# RF_REVE_2.net
KiCad netlist of a schematic drawn in Altium Designer
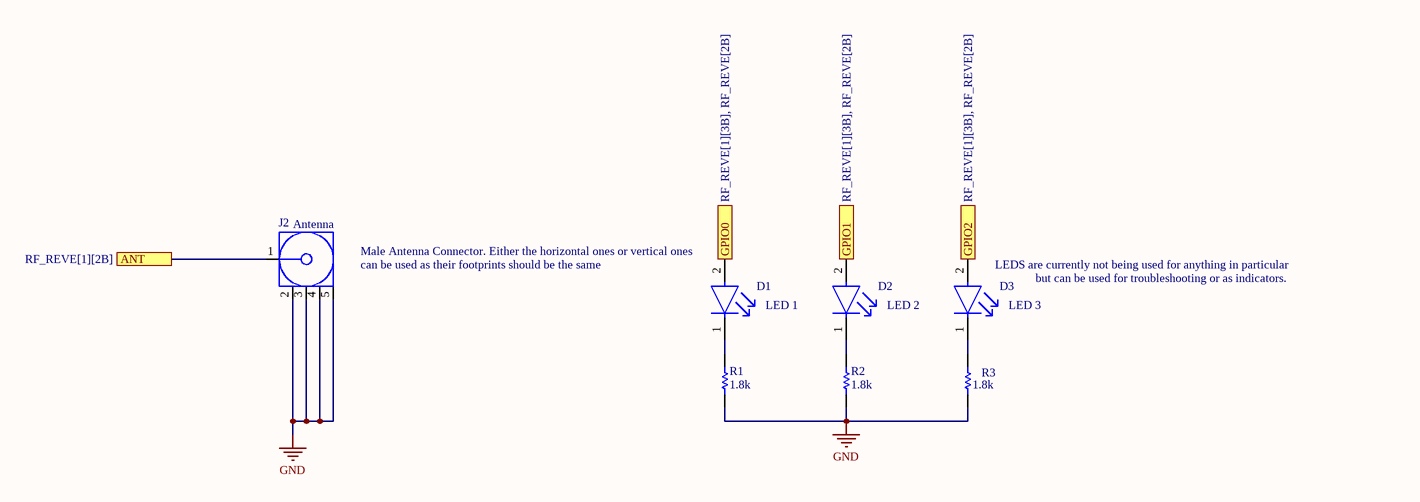
[diagram p0: RF_REVE[2].SchDoc]

(export (version "E")
  (design (tool "Eeschema 10.0.6"))
  (components
    (comp (ref "D1")
      (value "LED 1")
      (footprint "FP-APTD3216CGCK-MFG")
      (description "LED GREEN CLEAR 2SMD")
      (libsource (lib "Altium Content Vault") (part "8706943c75ba83719d021d2fdc84c58"))
    )
    (comp (ref "D2")
      (value "LED 2")
      (footprint "FP-APTD3216CGCK-MFG")
      (description "LED GREEN CLEAR 2SMD")
      (libsource (lib "Altium Content Vault") (part "8706943c75ba83719d021d2fdc84c58"))
    )
    (comp (ref "D3")
      (value "LED 3")
      (footprint "FP-APTD3216CGCK-MFG")
      (description "LED GREEN CLEAR 2SMD")
      (libsource (lib "Altium Content Vault") (part "8706943c75ba83719d021d2fdc84c58"))
    )
    (comp (ref "J2")
      (value "Antenna")
      (footprint "CINC-142-0701-801_V")
      (description "SMA End Launch Jack Receptacle, 50 Ohm, 0 to 18 GHz, -65 to 165 degC, 5-Pin SMD, RoHS, Bulk")
      (fields (field (name "MANUFACTURER") "EmersonConnectivitySolutions"))
      (libsource (lib "Altium Content Vault") (part "CN-S-4F-RF5"))
    )
    (comp (ref "R1")
      (value "1.8k")
      (footprint "RESC2013X60X35ML10T20")
      (fields (field (name "PART NUMBER") "RC0805FR-131K8L") (field (name "MANUFACTURER") "Yageo"))
      (libsource (lib "Altium Content Vault") (part "RES"))
    )
    (comp (ref "R2")
      (value "1.8k")
      (footprint "RESC2013X60X35ML10T20")
      (fields (field (name "PART NUMBER") "RC0805FR-131K8L") (field (name "MANUFACTURER") "Yageo"))
      (libsource (lib "Altium Content Vault") (part "RES"))
    )
    (comp (ref "R3")
      (value "1.8k")
      (footprint "RESC2013X60X35ML10T20")
      (fields (field (name "PART NUMBER") "RC0805FR-131K8L") (field (name "MANUFACTURER") "Yageo"))
      (libsource (lib "Altium Content Vault") (part "RES"))
    )
  )
  (nets
    (net (code "1") (name "/ANT") (class "Default")
      (node (ref "J2") (pin "1") (pinfunction "1_1") (pintype "passive"))
    )
    (net (code "2") (name "/GPIO0") (class "Default")
      (node (ref "D1") (pin "2") (pinfunction "A_2") (pintype "passive"))
    )
    (net (code "3") (name "/GPIO1") (class "Default")
      (node (ref "D2") (pin "2") (pinfunction "A_2") (pintype "passive"))
    )
    (net (code "4") (name "/GPIO2") (class "Default")
      (node (ref "D3") (pin "2") (pinfunction "A_2") (pintype "passive"))
    )
    (net (code "5") (name "GND") (class "Default")
      (node (ref "J2") (pin "2") (pinfunction "2_2") (pintype "passive"))
      (node (ref "J2") (pin "3") (pinfunction "3_3") (pintype "passive"))
      (node (ref "J2") (pin "4") (pinfunction "4_4") (pintype "passive"))
      (node (ref "J2") (pin "5") (pinfunction "5_5") (pintype "passive"))
      (node (ref "R1") (pin "1") (pinfunction "1_1") (pintype "passive"))
      (node (ref "R2") (pin "1") (pinfunction "1_1") (pintype "passive"))
      (node (ref "R3") (pin "1") (pinfunction "1_1") (pintype "passive"))
    )
    (net (code "6") (name "Net-(D1-C)") (class "Default")
      (node (ref "D1") (pin "1") (pinfunction "C_1") (pintype "passive"))
      (node (ref "R1") (pin "2") (pinfunction "2_2") (pintype "passive"))
    )
    (net (code "7") (name "Net-(D2-C)") (class "Default")
      (node (ref "D2") (pin "1") (pinfunction "C_1") (pintype "passive"))
      (node (ref "R2") (pin "2") (pinfunction "2_2") (pintype "passive"))
    )
    (net (code "8") (name "Net-(D3-C)") (class "Default")
      (node (ref "D3") (pin "1") (pinfunction "C_1") (pintype "passive"))
      (node (ref "R3") (pin "2") (pinfunction "2_2") (pintype "passive"))
    )
  )
)
